# DAC.net
KiCad netlist of a schematic drawn in Altium Designer
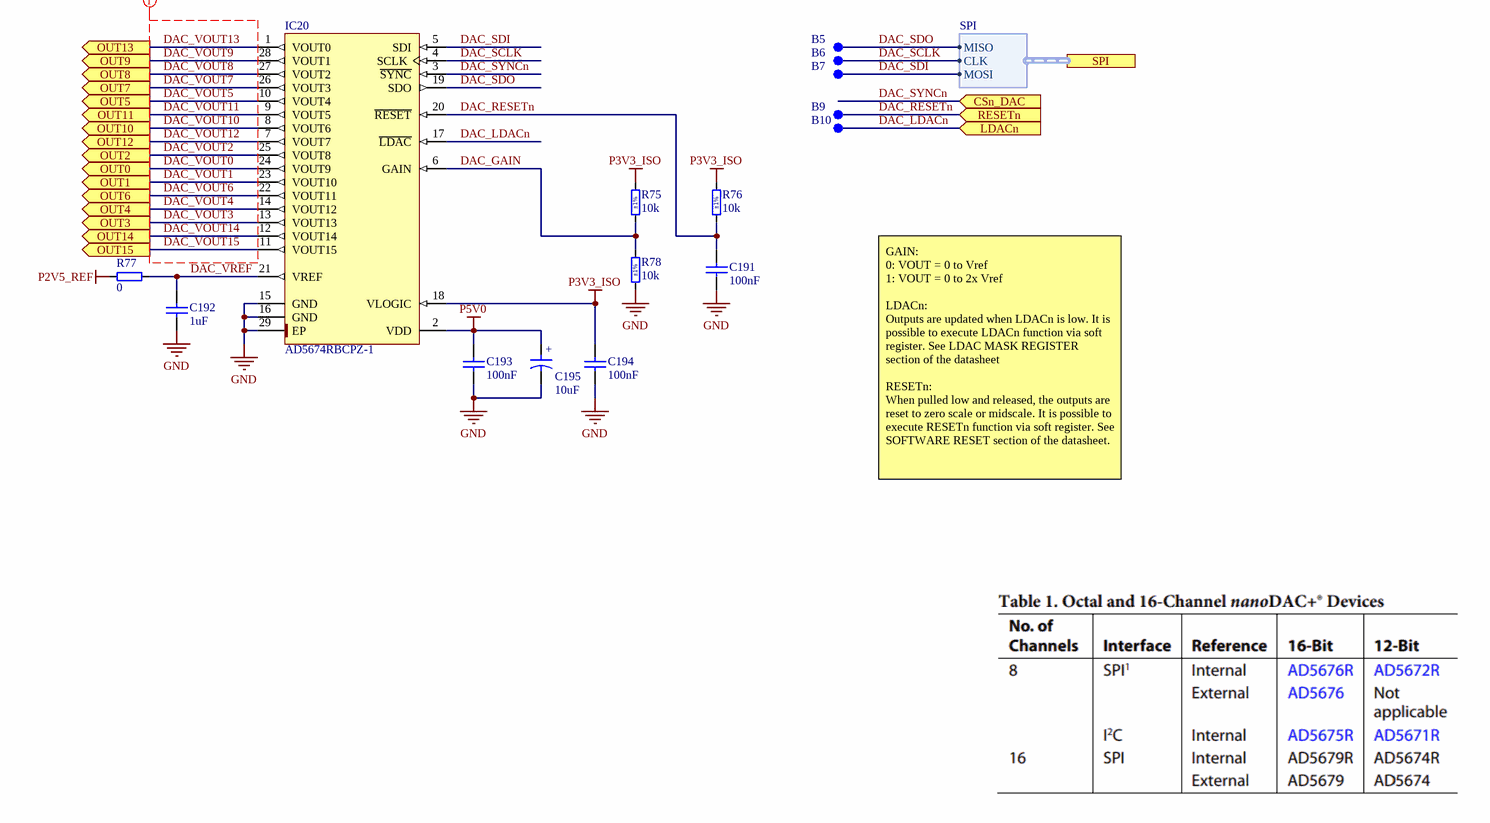
[diagram p0: DAC.SchDoc]

(export (version "E")
  (design (tool "Eeschema 10.0.6"))
  (components
    (comp (ref "B5")
      (value "SMD Pad")
      (footprint "C100")
      (description "Pad")
      (fields (field (name "PART NUMBER") "SMD_PAD_D1MM") (field (name "AUTHOR") "CERN DEM JLC"))
      (libsource (lib "Eletro-mechanical") (part "Single SMD Pad (Round)"))
    )
    (comp (ref "B6")
      (value "SMD Pad")
      (footprint "C100")
      (description "Pad")
      (fields (field (name "PART NUMBER") "SMD_PAD_D1MM") (field (name "AUTHOR") "CERN DEM JLC"))
      (libsource (lib "Eletro-mechanical") (part "Single SMD Pad (Round)"))
    )
    (comp (ref "B7")
      (value "SMD Pad")
      (footprint "C100")
      (description "Pad")
      (fields (field (name "PART NUMBER") "SMD_PAD_D1MM") (field (name "AUTHOR") "CERN DEM JLC"))
      (libsource (lib "Eletro-mechanical") (part "Single SMD Pad (Round)"))
    )
    (comp (ref "B9")
      (value "SMD Pad")
      (footprint "C100")
      (description "Pad")
      (fields (field (name "PART NUMBER") "SMD_PAD_D1MM") (field (name "AUTHOR") "CERN DEM JLC"))
      (libsource (lib "Eletro-mechanical") (part "Single SMD Pad (Round)"))
    )
    (comp (ref "B10")
      (value "SMD Pad")
      (footprint "C100")
      (description "Pad")
      (fields (field (name "PART NUMBER") "SMD_PAD_D1MM") (field (name "AUTHOR") "CERN DEM JLC"))
      (libsource (lib "Eletro-mechanical") (part "Single SMD Pad (Round)"))
    )
    (comp (ref "C191")
      (value "100nF")
      (footprint "CAPC1005X55N")
      (description "Non-polarised capacitor")
      (fields
        (field (name "PART NUMBER") "CC0402_100NF_50V_10%_X7R")
        (field (name "VOLTAGE") "50V")
        (field (name "AUTHOR") "CERN DEM MR")
      )
      (libsource (lib "Capacitors") (part "Capacitor - non polarized"))
    )
    (comp (ref "C192")
      (value "1uF")
      (footprint "CAPC1005X55N")
      (description "Non-polarised capacitor")
      (fields
        (field (name "PART NUMBER") "CC0402_1UF_16V_10%_X5R")
        (field (name "VOLTAGE") "16V")
        (field (name "AUTHOR") "CERN DEM JLC")
      )
      (libsource (lib "Capacitors") (part "Capacitor - non polarized"))
    )
    (comp (ref "C193")
      (value "100nF")
      (footprint "CAPC1005X55N")
      (description "Non-polarised capacitor")
      (fields
        (field (name "PART NUMBER") "CC0402_100NF_50V_10%_X7R")
        (field (name "VOLTAGE") "50V")
        (field (name "AUTHOR") "CERN DEM MR")
      )
      (libsource (lib "Capacitors") (part "Capacitor - non polarized"))
    )
    (comp (ref "C194")
      (value "100nF")
      (footprint "CAPC1005X55N")
      (description "Non-polarised capacitor")
      (fields
        (field (name "PART NUMBER") "CC0402_100NF_50V_10%_X7R")
        (field (name "VOLTAGE") "50V")
        (field (name "AUTHOR") "CERN DEM MR")
      )
      (libsource (lib "Capacitors") (part "Capacitor - non polarized"))
    )
    (comp (ref "C195")
      (value "10uF")
      (footprint "CAPMP3216X180N")
      (description "Polarised capacitor")
      (fields
        (field (name "PART NUMBER") "CTE3216-18_10UF_16V_20%_AVX_TCJ")
        (field (name "VOLTAGE") "16V")
        (field (name "AUTHOR") "CERN DEM JLC")
      )
      (libsource (lib "Capacitors") (part "Capacitor - polarized"))
    )
    (comp (ref "IC20")
      (value "AD5674RBCPZ-1")
      (footprint "QFN40P400X400X100-29N-S270")
      (description "12-Bit nanoDAC+ with 2 ppm/°C Voltage Reference Temperature Coefficient, SPI Interface")
      (fields (field (name "MANUFACTURER") "ANALOG DEVICES") (field (name "AUTHOR") "CERN DEM HF"))
      (libsource (lib "ICs And Semiconductors") (part "AD5674RBCPZ-1"))
    )
    (comp (ref "R75")
      (value "10k")
      (footprint "RESC1005X40N")
      (description "Resistor - 1%")
      (fields
        (field (name "TOLERANCE") "±1%")
        (field (name "PART NUMBER") "R0402_10K_1%_0.0625W_100PPM")
        (field (name "POWER") "0.0625W")
        (field (name "AUTHOR") "CERN DEM JLC")
      )
      (libsource (lib "Resistors") (part "Resistor - 1%"))
    )
    (comp (ref "R76")
      (value "10k")
      (footprint "RESC1005X40N")
      (description "Resistor - 1%")
      (fields
        (field (name "TOLERANCE") "±1%")
        (field (name "PART NUMBER") "R0402_10K_1%_0.0625W_100PPM")
        (field (name "POWER") "0.0625W")
        (field (name "AUTHOR") "CERN DEM JLC")
      )
      (libsource (lib "Resistors") (part "Resistor - 1%"))
    )
    (comp (ref "R77")
      (value "0")
      (footprint "RESC1005X40N")
      (description "Resistor")
      (fields
        (field (name "PART NUMBER") "R0402_0R_JUMPER")
        (field (name "MANUFACTURER") "GENERIC")
        (field (name "AUTHOR") "CERN DEM JLC")
      )
      (libsource (lib "Resistors") (part "Resistor"))
    )
    (comp (ref "R78")
      (value "10k")
      (footprint "RESC1005X40N")
      (description "Resistor - 1%")
      (fields
        (field (name "TOLERANCE") "±1%")
        (field (name "PART NUMBER") "R0402_10K_1%_0.0625W_100PPM")
        (field (name "POWER") "0.0625W")
        (field (name "AUTHOR") "CERN DEM JLC")
      )
      (libsource (lib "Resistors") (part "Resistor - 1%"))
    )
  )
  (nets
    (net (code "2") (name "/DAC_GAIN") (class "Default")
      (node (ref "IC20") (pin "6") (pinfunction "GAIN_6") (pintype "input"))
      (node (ref "R75") (pin "1") (pinfunction "1_1") (pintype "passive"))
      (node (ref "R78") (pin "2") (pinfunction "2_2") (pintype "passive"))
    )
    (net (code "3") (name "/DAC_LDACn") (class "Default")
      (node (ref "B10") (pin "1") (pinfunction "1_1") (pintype "bidirectional"))
      (node (ref "IC20") (pin "17") (pinfunction "~{LDAC}_17") (pintype "input"))
    )
    (net (code "4") (name "/DAC_RESETn") (class "Default")
      (node (ref "B9") (pin "1") (pinfunction "1_1") (pintype "bidirectional"))
      (node (ref "C191") (pin "2") (pinfunction "2_2") (pintype "passive"))
      (node (ref "IC20") (pin "20") (pinfunction "~{RESET}_20") (pintype "input"))
      (node (ref "R76") (pin "1") (pinfunction "1_1") (pintype "passive"))
    )
    (net (code "5") (name "/DAC_SCLK") (class "Default")
      (node (ref "B6") (pin "1") (pinfunction "1_1") (pintype "bidirectional"))
      (node (ref "IC20") (pin "4") (pinfunction "SCLK_4") (pintype "input"))
    )
    (net (code "6") (name "/DAC_SDI") (class "Default")
      (node (ref "B7") (pin "1") (pinfunction "1_1") (pintype "bidirectional"))
      (node (ref "IC20") (pin "5") (pinfunction "SDI_5") (pintype "input"))
    )
    (net (code "7") (name "/DAC_SDO") (class "Default")
      (node (ref "B5") (pin "1") (pinfunction "1_1") (pintype "bidirectional"))
      (node (ref "IC20") (pin "19") (pinfunction "SDO_19") (pintype "output"))
    )
    (net (code "8") (name "/DAC_SYNCn") (class "Default")
      (node (ref "IC20") (pin "3") (pinfunction "~{SYNC}_3") (pintype "input"))
    )
    (net (code "9") (name "/DAC_VOUT0") (class "Default")
      (node (ref "IC20") (pin "24") (pinfunction "VOUT9_24") (pintype "output"))
    )
    (net (code "10") (name "/DAC_VOUT1") (class "Default")
      (node (ref "IC20") (pin "23") (pinfunction "VOUT10_23") (pintype "output"))
    )
    (net (code "11") (name "/DAC_VOUT2") (class "Default")
      (node (ref "IC20") (pin "25") (pinfunction "VOUT8_25") (pintype "output"))
    )
    (net (code "12") (name "/DAC_VOUT3") (class "Default")
      (node (ref "IC20") (pin "13") (pinfunction "VOUT13_13") (pintype "output"))
    )
    (net (code "13") (name "/DAC_VOUT4") (class "Default")
      (node (ref "IC20") (pin "14") (pinfunction "VOUT12_14") (pintype "output"))
    )
    (net (code "14") (name "/DAC_VOUT5") (class "Default")
      (node (ref "IC20") (pin "10") (pinfunction "VOUT4_10") (pintype "output"))
    )
    (net (code "15") (name "/DAC_VOUT6") (class "Default")
      (node (ref "IC20") (pin "22") (pinfunction "VOUT11_22") (pintype "output"))
    )
    (net (code "16") (name "/DAC_VOUT7") (class "Default")
      (node (ref "IC20") (pin "26") (pinfunction "VOUT3_26") (pintype "output"))
    )
    (net (code "17") (name "/DAC_VOUT8") (class "Default")
      (node (ref "IC20") (pin "27") (pinfunction "VOUT2_27") (pintype "output"))
    )
    (net (code "18") (name "/DAC_VOUT9") (class "Default")
      (node (ref "IC20") (pin "28") (pinfunction "VOUT1_28") (pintype "output"))
    )
    (net (code "19") (name "/DAC_VOUT10") (class "Default")
      (node (ref "IC20") (pin "8") (pinfunction "VOUT6_8") (pintype "output"))
    )
    (net (code "20") (name "/DAC_VOUT11") (class "Default")
      (node (ref "IC20") (pin "9") (pinfunction "VOUT5_9") (pintype "output"))
    )
    (net (code "21") (name "/DAC_VOUT12") (class "Default")
      (node (ref "IC20") (pin "7") (pinfunction "VOUT7_7") (pintype "output"))
    )
    (net (code "22") (name "/DAC_VOUT13") (class "Default")
      (node (ref "IC20") (pin "1") (pinfunction "VOUT0_1") (pintype "output"))
    )
    (net (code "23") (name "/DAC_VOUT14") (class "Default")
      (node (ref "IC20") (pin "12") (pinfunction "VOUT14_12") (pintype "output"))
    )
    (net (code "24") (name "/DAC_VOUT15") (class "Default")
      (node (ref "IC20") (pin "11") (pinfunction "VOUT15_11") (pintype "output"))
    )
    (net (code "25") (name "/DAC_VREF") (class "Default")
      (node (ref "C192") (pin "2") (pinfunction "2_2") (pintype "passive"))
      (node (ref "IC20") (pin "21") (pinfunction "VREF_21") (pintype "output"))
      (node (ref "R77") (pin "2") (pinfunction "2_2") (pintype "passive"))
    )
    (net (code "27") (name "GND") (class "Default")
      (node (ref "C191") (pin "1") (pinfunction "1_1") (pintype "passive"))
      (node (ref "C192") (pin "1") (pinfunction "1_1") (pintype "passive"))
      (node (ref "C193") (pin "1") (pinfunction "1_1") (pintype "passive"))
      (node (ref "C194") (pin "1") (pinfunction "1_1") (pintype "passive"))
      (node (ref "C195") (pin "2") (pinfunction "2_2") (pintype "passive"))
      (node (ref "IC20") (pin "15") (pinfunction "GND_15") (pintype "power_in"))
      (node (ref "IC20") (pin "16") (pinfunction "GND_16") (pintype "power_in"))
      (node (ref "IC20") (pin "29") (pinfunction "EP_29") (pintype "power_in"))
      (node (ref "R78") (pin "1") (pinfunction "1_1") (pintype "passive"))
    )
    (net (code "28") (name "P2V5_REF") (class "Default")
      (node (ref "R77") (pin "1") (pinfunction "1_1") (pintype "passive"))
    )
    (net (code "29") (name "P3V3_ISO") (class "Default")
      (node (ref "C194") (pin "2") (pinfunction "2_2") (pintype "passive"))
      (node (ref "IC20") (pin "18") (pinfunction "VLOGIC_18") (pintype "input"))
      (node (ref "R75") (pin "2") (pinfunction "2_2") (pintype "passive"))
      (node (ref "R76") (pin "2") (pinfunction "2_2") (pintype "passive"))
    )
    (net (code "30") (name "P5V0") (class "Default")
      (node (ref "C193") (pin "2") (pinfunction "2_2") (pintype "passive"))
      (node (ref "C195") (pin "1") (pinfunction "1_1") (pintype "passive"))
      (node (ref "IC20") (pin "2") (pinfunction "VDD_2") (pintype "power_in"))
    )
  )
)
